# circuit-connections.net
KiCad netlist of a schematic drawn in EasyEDA
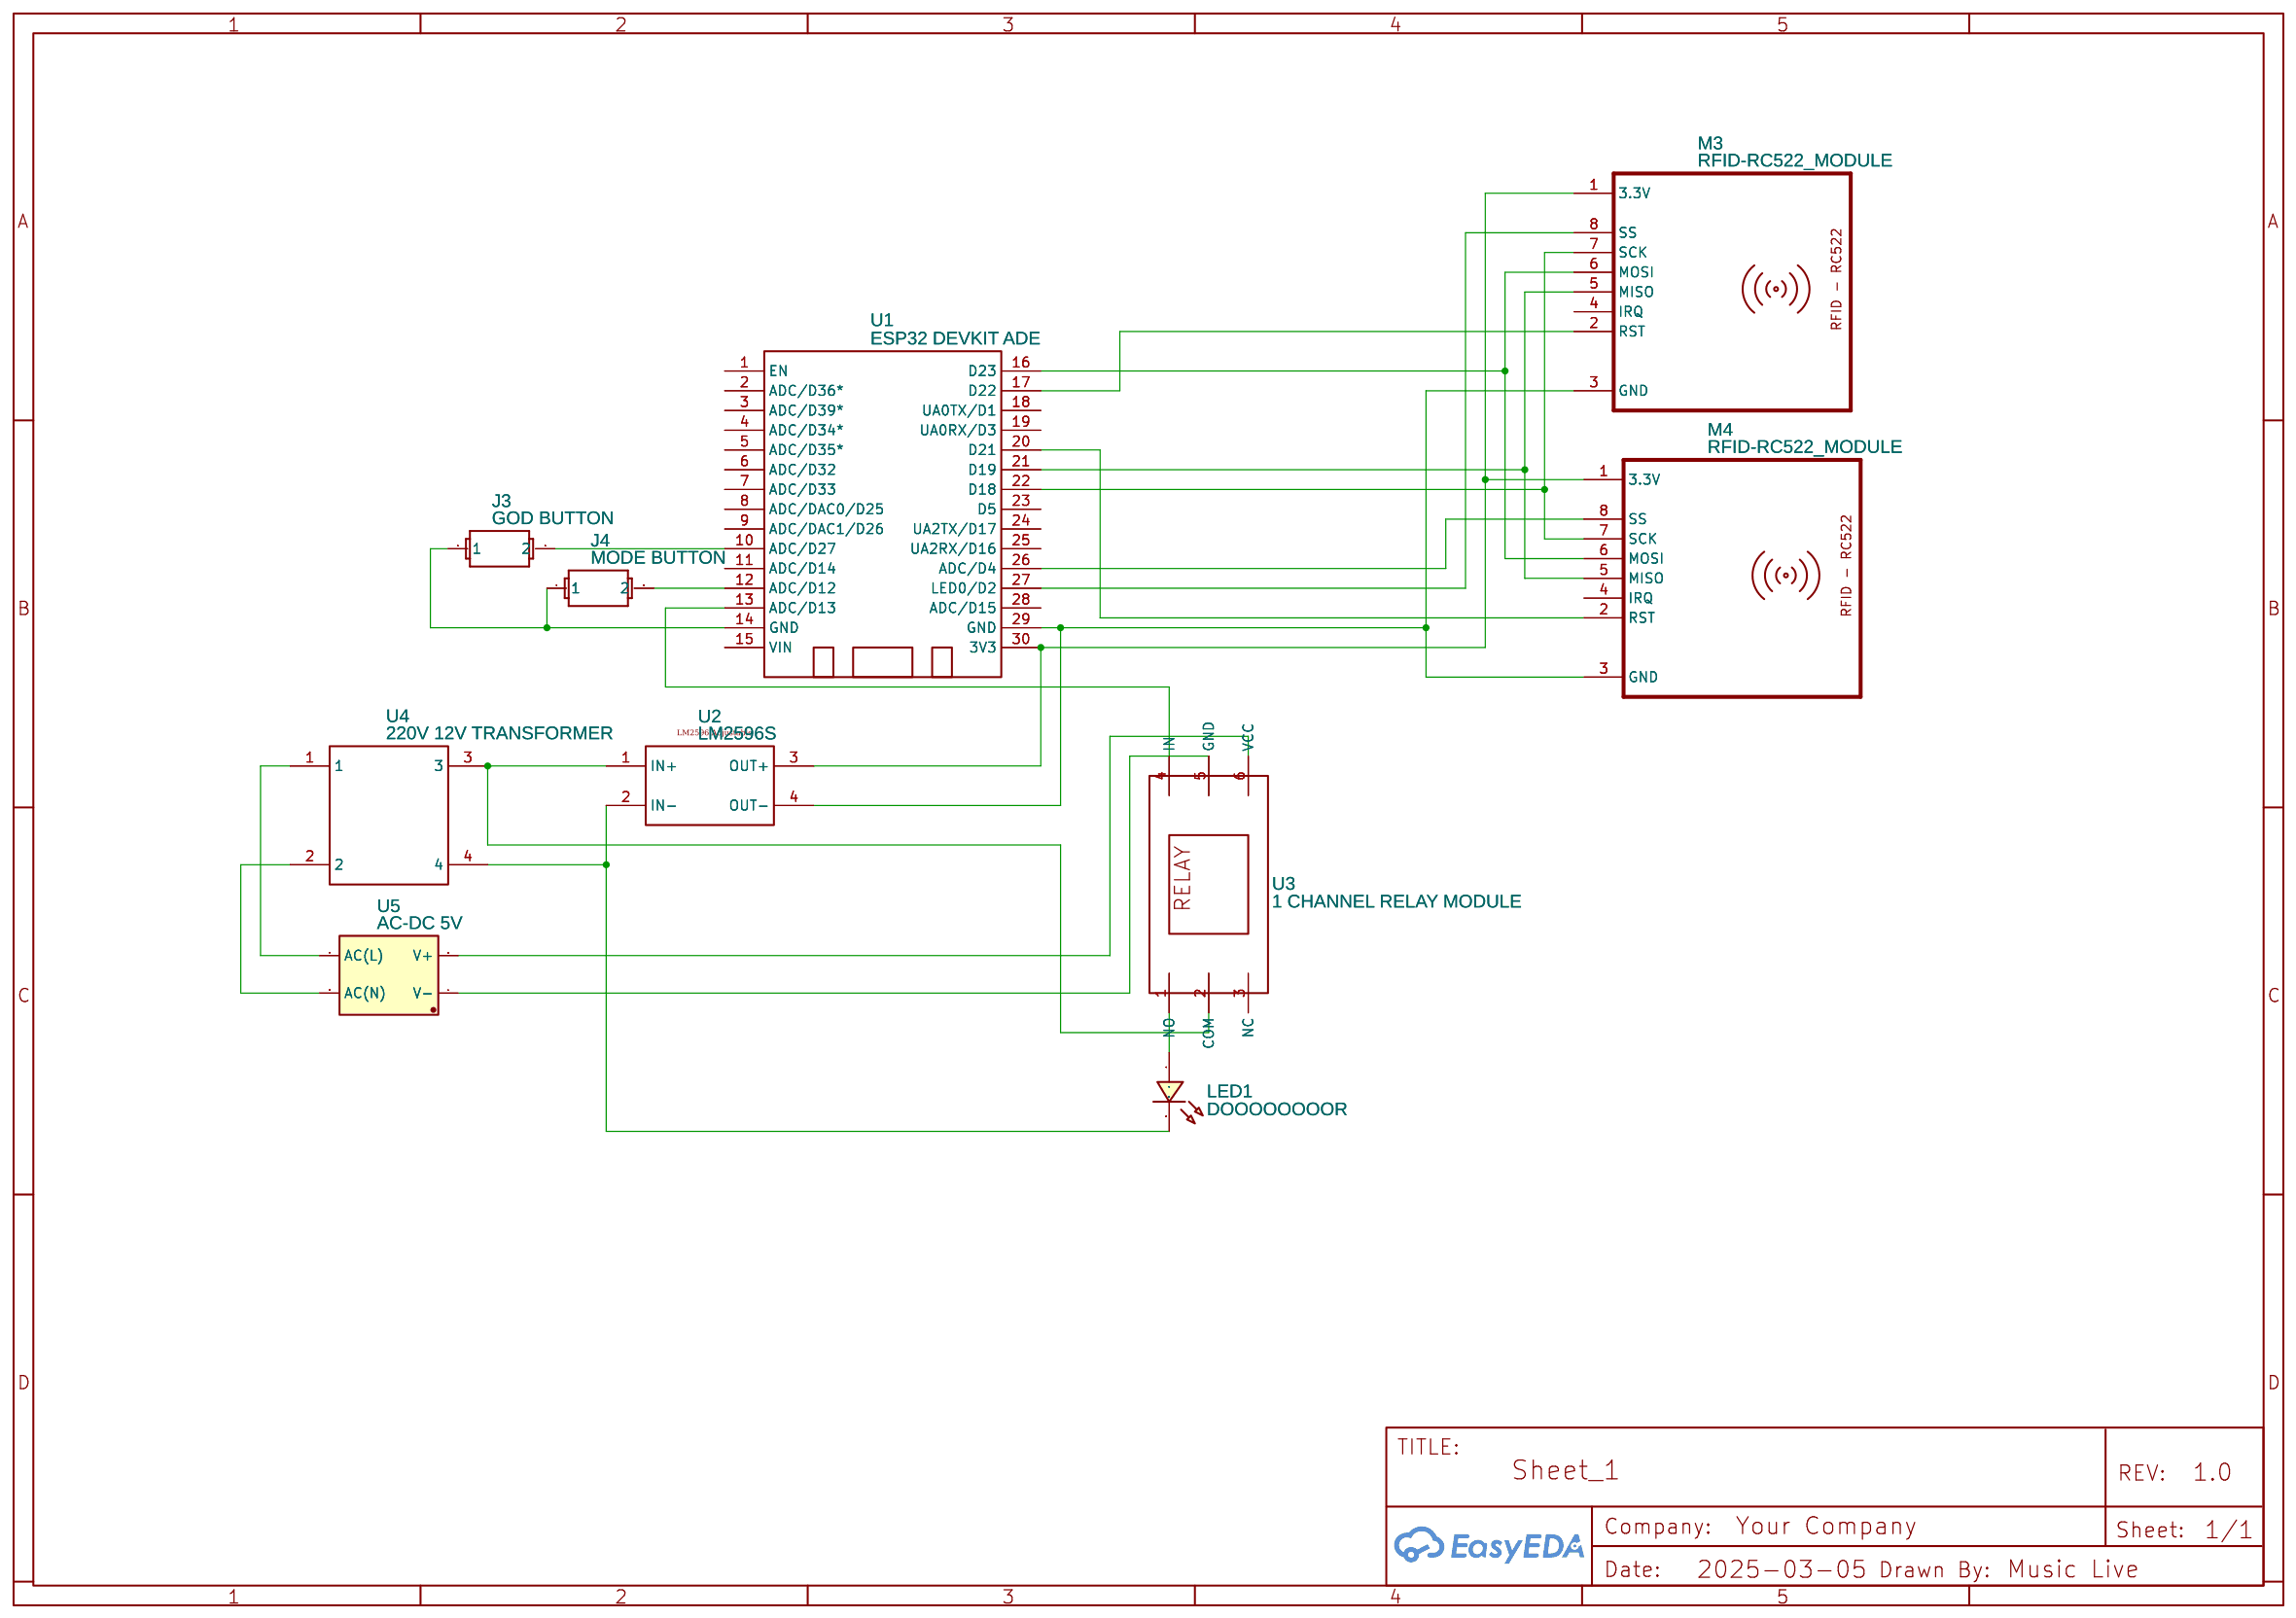
[diagram p0: schematic sheet]

(export (version "E")
  (design (tool "Eeschema 10.0.6"))
  (components
    (comp (ref "J3") (value "GOD BUTTON") (libsource (lib "") (part "BUTTON_TD1183SA_BUTTON_TD1183SA")))
    (comp (ref "J4") (value "MODE BUTTON") (libsource (lib "") (part "BUTTON_TD1183SA_BUTTON_TD1183SA")))
    (comp (ref "LED1")
      (value "DOOOOOOOOR")
      (fields
        (field (name "Manufacturer Part") "19-217/R6C-AL1M2VY/3T")
        (field (name "Manufacturer") "EVERLIGHT(台湾亿光)")
      )
      (libsource (lib "") (part "LED-0603_R"))
    )
    (comp (ref "M3") (value "RFID-RC522_MODULE") (libsource (lib "") (part "RFID-RC522_MODULE")))
    (comp (ref "M4") (value "RFID-RC522_MODULE") (libsource (lib "") (part "RFID-RC522_MODULE")))
    (comp (ref "U1") (value "ESP32 DEVKIT ADE") (libsource (lib "") (part "ESP32 DEVKIT ADE")))
    (comp (ref "U2") (value "LM2596S") (libsource (lib "") (part "BuckConverters_LM2596_Adj")))
    (comp (ref "U3") (value "1 CHANNEL RELAY MODULE") (libsource (lib "") (part "1 CHANNEL RELAY MODULE")))
    (comp (ref "U4") (value "220V 12V TRANSFORMER") (libsource (lib "") (part "220V 12V TRANSFORMER")))
    (comp (ref "U5")
      (value "AC-DC 5V")
      (fields (field (name "Manufacturer Part") "AC-DC 5v 700mA") (field (name "Manufacturer") "HIECUBE"))
      (libsource (lib "") (part "AC-DC 5V"))
    )
  )
  (nets
    (net (code "1") (name "Net-(J3-Pad1)") (class "Default")
      (node (ref "J3") (pin "1") (pinfunction "1_1") (pintype "bidirectional"))
      (node (ref "J4") (pin "1") (pinfunction "1_1") (pintype "bidirectional"))
      (node (ref "U1") (pin "14") (pinfunction "GND_14") (pintype "bidirectional"))
    )
    (net (code "2") (name "Net-(M3-3.3V)") (class "Default")
      (node (ref "M3") (pin "1") (pinfunction "3.3V_1") (pintype "unspecified"))
      (node (ref "M4") (pin "1") (pinfunction "3.3V_1") (pintype "unspecified"))
      (node (ref "U1") (pin "30") (pinfunction "3V3_30") (pintype "bidirectional"))
      (node (ref "U2") (pin "3") (pinfunction "OUT+_3") (pintype "unspecified"))
    )
    (net (code "3") (name "Net-(M3-GND)") (class "Default")
      (node (ref "M3") (pin "3") (pinfunction "GND_3") (pintype "unspecified"))
      (node (ref "M4") (pin "3") (pinfunction "GND_3") (pintype "unspecified"))
      (node (ref "U1") (pin "29") (pinfunction "GND_29") (pintype "bidirectional"))
      (node (ref "U2") (pin "4") (pinfunction "OUT-_4") (pintype "unspecified"))
    )
    (net (code "4") (name "Net-(M3-MISO)") (class "Default")
      (node (ref "M3") (pin "5") (pinfunction "MISO_5") (pintype "unspecified"))
      (node (ref "M4") (pin "5") (pinfunction "MISO_5") (pintype "unspecified"))
      (node (ref "U1") (pin "21") (pinfunction "D19_21") (pintype "bidirectional"))
    )
    (net (code "5") (name "Net-(M3-MOSI)") (class "Default")
      (node (ref "M3") (pin "6") (pinfunction "MOSI_6") (pintype "unspecified"))
      (node (ref "M4") (pin "6") (pinfunction "MOSI_6") (pintype "unspecified"))
      (node (ref "U1") (pin "16") (pinfunction "D23_16") (pintype "bidirectional"))
    )
    (net (code "6") (name "Net-(M3-RST)") (class "Default")
      (node (ref "M3") (pin "2") (pinfunction "RST_2") (pintype "unspecified"))
      (node (ref "U1") (pin "17") (pinfunction "D22_17") (pintype "bidirectional"))
    )
    (net (code "7") (name "Net-(M3-SCK)") (class "Default")
      (node (ref "M3") (pin "7") (pinfunction "SCK_7") (pintype "unspecified"))
      (node (ref "M4") (pin "7") (pinfunction "SCK_7") (pintype "unspecified"))
      (node (ref "U1") (pin "22") (pinfunction "D18_22") (pintype "bidirectional"))
    )
    (net (code "8") (name "Net-(M3-SS)") (class "Default")
      (node (ref "M3") (pin "8") (pinfunction "SS_8") (pintype "unspecified"))
      (node (ref "U1") (pin "27") (pinfunction "LED0/D2_27") (pintype "bidirectional"))
    )
    (net (code "9") (name "Net-(M4-RST)") (class "Default")
      (node (ref "M4") (pin "2") (pinfunction "RST_2") (pintype "unspecified"))
      (node (ref "U1") (pin "20") (pinfunction "D21_20") (pintype "bidirectional"))
    )
    (net (code "10") (name "Net-(M4-SS)") (class "Default")
      (node (ref "M4") (pin "8") (pinfunction "SS_8") (pintype "unspecified"))
      (node (ref "U1") (pin "26") (pinfunction "ADC/D4_26") (pintype "bidirectional"))
    )
    (net (code "11") (name "Net-(U1-ADC{slash}D12)") (class "Default")
      (node (ref "J4") (pin "2") (pinfunction "2_2") (pintype "bidirectional"))
      (node (ref "U1") (pin "12") (pinfunction "ADC/D12_12") (pintype "bidirectional"))
    )
    (net (code "12") (name "Net-(U1-ADC{slash}D13)") (class "Default")
      (node (ref "U1") (pin "13") (pinfunction "ADC/D13_13") (pintype "bidirectional"))
      (node (ref "U3") (pin "4") (pinfunction "IN_4") (pintype "unspecified"))
    )
    (net (code "13") (name "Net-(U1-ADC{slash}D27)") (class "Default")
      (node (ref "J3") (pin "2") (pinfunction "2_2") (pintype "bidirectional"))
      (node (ref "U1") (pin "10") (pinfunction "ADC/D27_10") (pintype "bidirectional"))
    )
    (net (code "14") (name "Net-(U2-IN+)") (class "Default")
      (node (ref "U2") (pin "1") (pinfunction "IN+_1") (pintype "unspecified"))
      (node (ref "U3") (pin "2") (pinfunction "COM_2") (pintype "unspecified"))
      (node (ref "U4") (pin "3") (pinfunction "3_3") (pintype "unspecified"))
    )
    (net (code "15") (name "Net-(U2-IN-)") (class "Default")
      (node (ref "LED1") (pin "2") (pinfunction "2_2") (pintype "unspecified"))
      (node (ref "U2") (pin "2") (pinfunction "IN-_2") (pintype "unspecified"))
      (node (ref "U4") (pin "4") (pinfunction "4_4") (pintype "unspecified"))
    )
    (net (code "16") (name "Net-(U3-GND)") (class "Default")
      (node (ref "U3") (pin "5") (pinfunction "GND_5") (pintype "unspecified"))
      (node (ref "U5") (pin "4") (pinfunction "V-_4") (pintype "unspecified"))
    )
    (net (code "17") (name "Net-(U3-NO)") (class "Default")
      (node (ref "LED1") (pin "1") (pinfunction "1_1") (pintype "unspecified"))
      (node (ref "U3") (pin "1") (pinfunction "NO_1") (pintype "unspecified"))
    )
    (net (code "18") (name "Net-(U3-VCC)") (class "Default")
      (node (ref "U3") (pin "6") (pinfunction "VCC_6") (pintype "unspecified"))
      (node (ref "U5") (pin "3") (pinfunction "V+_3") (pintype "unspecified"))
    )
    (net (code "19") (name "Net-(U5-AC(L))") (class "Default")
      (node (ref "U4") (pin "1") (pinfunction "1_1") (pintype "unspecified"))
      (node (ref "U5") (pin "1") (pinfunction "AC(L)_1") (pintype "unspecified"))
    )
    (net (code "20") (name "Net-(U5-AC(N))") (class "Default")
      (node (ref "U4") (pin "2") (pinfunction "2_2") (pintype "unspecified"))
      (node (ref "U5") (pin "2") (pinfunction "AC(N)_2") (pintype "unspecified"))
    )
    (net (code "21") (name "unconnected-(M3-IRQ-Pad4)") (class "Default")
      (node (ref "M3") (pin "4") (pinfunction "IRQ_4") (pintype "unspecified"))
    )
    (net (code "22") (name "unconnected-(M4-IRQ-Pad4)") (class "Default")
      (node (ref "M4") (pin "4") (pinfunction "IRQ_4") (pintype "unspecified"))
    )
    (net (code "23") (name "unconnected-(U1-ADC{slash}D14-Pad11)") (class "Default")
      (node (ref "U1") (pin "11") (pinfunction "ADC/D14_11") (pintype "bidirectional"))
    )
    (net (code "24") (name "unconnected-(U1-ADC{slash}D15-Pad28)") (class "Default")
      (node (ref "U1") (pin "28") (pinfunction "ADC/D15_28") (pintype "bidirectional"))
    )
    (net (code "25") (name "unconnected-(U1-ADC{slash}D32-Pad6)") (class "Default")
      (node (ref "U1") (pin "6") (pinfunction "ADC/D32_6") (pintype "bidirectional"))
    )
    (net (code "26") (name "unconnected-(U1-ADC{slash}D33-Pad7)") (class "Default")
      (node (ref "U1") (pin "7") (pinfunction "ADC/D33_7") (pintype "bidirectional"))
    )
    (net (code "27") (name "unconnected-(U1-ADC{slash}D34*-Pad4)") (class "Default")
      (node (ref "U1") (pin "4") (pinfunction "ADC/D34*_4") (pintype "input"))
    )
    (net (code "28") (name "unconnected-(U1-ADC{slash}D35*-Pad5)") (class "Default")
      (node (ref "U1") (pin "5") (pinfunction "ADC/D35*_5") (pintype "input"))
    )
    (net (code "29") (name "unconnected-(U1-ADC{slash}D36*-Pad2)") (class "Default")
      (node (ref "U1") (pin "2") (pinfunction "ADC/D36*_2") (pintype "input"))
    )
    (net (code "30") (name "unconnected-(U1-ADC{slash}D39*-Pad3)") (class "Default")
      (node (ref "U1") (pin "3") (pinfunction "ADC/D39*_3") (pintype "input"))
    )
    (net (code "31") (name "unconnected-(U1-ADC{slash}DAC0{slash}D25-Pad8)") (class "Default")
      (node (ref "U1") (pin "8") (pinfunction "ADC/DAC0/D25_8") (pintype "bidirectional"))
    )
    (net (code "32") (name "unconnected-(U1-ADC{slash}DAC1{slash}D26-Pad9)") (class "Default")
      (node (ref "U1") (pin "9") (pinfunction "ADC/DAC1/D26_9") (pintype "bidirectional"))
    )
    (net (code "33") (name "unconnected-(U1-D5-Pad23)") (class "Default")
      (node (ref "U1") (pin "23") (pinfunction "D5_23") (pintype "bidirectional"))
    )
    (net (code "34") (name "unconnected-(U1-EN-Pad1)") (class "Default")
      (node (ref "U1") (pin "1") (pinfunction "EN_1") (pintype "bidirectional"))
    )
    (net (code "35") (name "unconnected-(U1-UA0RX{slash}D3-Pad19)") (class "Default")
      (node (ref "U1") (pin "19") (pinfunction "UA0RX/D3_19") (pintype "bidirectional"))
    )
    (net (code "36") (name "unconnected-(U1-UA0TX{slash}D1-Pad18)") (class "Default")
      (node (ref "U1") (pin "18") (pinfunction "UA0TX/D1_18") (pintype "bidirectional"))
    )
    (net (code "37") (name "unconnected-(U1-UA2RX{slash}D16-Pad25)") (class "Default")
      (node (ref "U1") (pin "25") (pinfunction "UA2RX/D16_25") (pintype "bidirectional"))
    )
    (net (code "38") (name "unconnected-(U1-UA2TX{slash}D17-Pad24)") (class "Default")
      (node (ref "U1") (pin "24") (pinfunction "UA2TX/D17_24") (pintype "bidirectional"))
    )
    (net (code "39") (name "unconnected-(U1-VIN-Pad15)") (class "Default")
      (node (ref "U1") (pin "15") (pinfunction "VIN_15") (pintype "input"))
    )
    (net (code "40") (name "unconnected-(U3-NC-Pad3)") (class "Default")
      (node (ref "U3") (pin "3") (pinfunction "NC_3") (pintype "unspecified"))
    )
  )
)
